# PDT3535LEDbackup.net
KiCad netlist of a schematic drawn in EAGLE
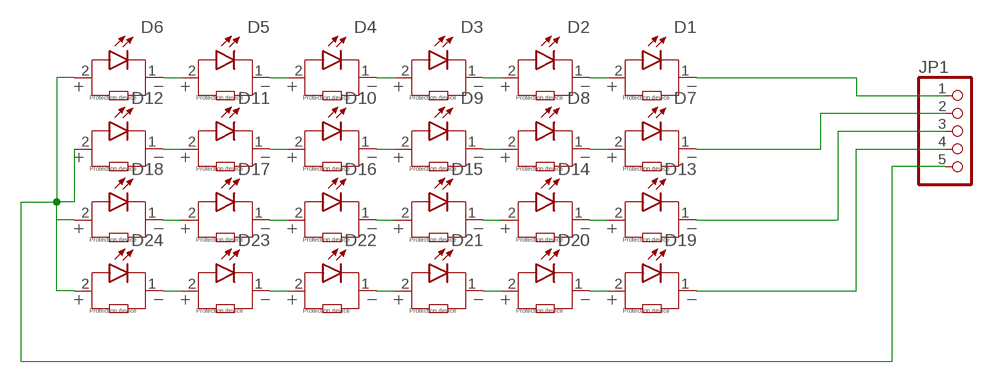
[diagram p0: schematic, sheet 1]

(export (version "E")
  (design (tool "Eeschema 10.0.6"))
  (components
    (comp (ref "D1")
      (value "WL-SWTC_3535_158353060_6000K")
      (footprint "eagle-import:WL-SWTC_3535")
      (libsource (lib "eagle-import") (part "WL-SWTC_3535_158353060_6000K"))
    )
    (comp (ref "D2")
      (value "WL-SWTC_3535_158353060_6000K")
      (footprint "eagle-import:WL-SWTC_3535")
      (libsource (lib "eagle-import") (part "WL-SWTC_3535_158353060_6000K"))
    )
    (comp (ref "D3")
      (value "WL-SWTC_3535_158353060_6000K")
      (footprint "eagle-import:WL-SWTC_3535")
      (libsource (lib "eagle-import") (part "WL-SWTC_3535_158353060_6000K"))
    )
    (comp (ref "D4")
      (value "WL-SWTC_3535_158353060_6000K")
      (footprint "eagle-import:WL-SWTC_3535")
      (libsource (lib "eagle-import") (part "WL-SWTC_3535_158353060_6000K"))
    )
    (comp (ref "D5")
      (value "WL-SWTC_3535_158353060_6000K")
      (footprint "eagle-import:WL-SWTC_3535")
      (libsource (lib "eagle-import") (part "WL-SWTC_3535_158353060_6000K"))
    )
    (comp (ref "D6")
      (value "WL-SWTC_3535_158353060_6000K")
      (footprint "eagle-import:WL-SWTC_3535")
      (libsource (lib "eagle-import") (part "WL-SWTC_3535_158353060_6000K"))
    )
    (comp (ref "D7")
      (value "WL-SWTC_3535_158353060_6000K")
      (footprint "eagle-import:WL-SWTC_3535")
      (libsource (lib "eagle-import") (part "WL-SWTC_3535_158353060_6000K"))
    )
    (comp (ref "D8")
      (value "WL-SWTC_3535_158353060_6000K")
      (footprint "eagle-import:WL-SWTC_3535")
      (libsource (lib "eagle-import") (part "WL-SWTC_3535_158353060_6000K"))
    )
    (comp (ref "D9")
      (value "WL-SWTC_3535_158353060_6000K")
      (footprint "eagle-import:WL-SWTC_3535")
      (libsource (lib "eagle-import") (part "WL-SWTC_3535_158353060_6000K"))
    )
    (comp (ref "D10")
      (value "WL-SWTC_3535_158353060_6000K")
      (footprint "eagle-import:WL-SWTC_3535")
      (libsource (lib "eagle-import") (part "WL-SWTC_3535_158353060_6000K"))
    )
    (comp (ref "D11")
      (value "WL-SWTC_3535_158353060_6000K")
      (footprint "eagle-import:WL-SWTC_3535")
      (libsource (lib "eagle-import") (part "WL-SWTC_3535_158353060_6000K"))
    )
    (comp (ref "D12")
      (value "WL-SWTC_3535_158353060_6000K")
      (footprint "eagle-import:WL-SWTC_3535")
      (libsource (lib "eagle-import") (part "WL-SWTC_3535_158353060_6000K"))
    )
    (comp (ref "D13")
      (value "WL-SWTC_3535_158353060_6000K")
      (footprint "eagle-import:WL-SWTC_3535")
      (libsource (lib "eagle-import") (part "WL-SWTC_3535_158353060_6000K"))
    )
    (comp (ref "D14")
      (value "WL-SWTC_3535_158353060_6000K")
      (footprint "eagle-import:WL-SWTC_3535")
      (libsource (lib "eagle-import") (part "WL-SWTC_3535_158353060_6000K"))
    )
    (comp (ref "D15")
      (value "WL-SWTC_3535_158353060_6000K")
      (footprint "eagle-import:WL-SWTC_3535")
      (libsource (lib "eagle-import") (part "WL-SWTC_3535_158353060_6000K"))
    )
    (comp (ref "D16")
      (value "WL-SWTC_3535_158353060_6000K")
      (footprint "eagle-import:WL-SWTC_3535")
      (libsource (lib "eagle-import") (part "WL-SWTC_3535_158353060_6000K"))
    )
    (comp (ref "D17")
      (value "WL-SWTC_3535_158353060_6000K")
      (footprint "eagle-import:WL-SWTC_3535")
      (libsource (lib "eagle-import") (part "WL-SWTC_3535_158353060_6000K"))
    )
    (comp (ref "D18")
      (value "WL-SWTC_3535_158353060_6000K")
      (footprint "eagle-import:WL-SWTC_3535")
      (libsource (lib "eagle-import") (part "WL-SWTC_3535_158353060_6000K"))
    )
    (comp (ref "D19")
      (value "WL-SWTC_3535_158353060_6000K")
      (footprint "eagle-import:WL-SWTC_3535")
      (libsource (lib "eagle-import") (part "WL-SWTC_3535_158353060_6000K"))
    )
    (comp (ref "D20")
      (value "WL-SWTC_3535_158353060_6000K")
      (footprint "eagle-import:WL-SWTC_3535")
      (libsource (lib "eagle-import") (part "WL-SWTC_3535_158353060_6000K"))
    )
    (comp (ref "D21")
      (value "WL-SWTC_3535_158353060_6000K")
      (footprint "eagle-import:WL-SWTC_3535")
      (libsource (lib "eagle-import") (part "WL-SWTC_3535_158353060_6000K"))
    )
    (comp (ref "D22")
      (value "WL-SWTC_3535_158353060_6000K")
      (footprint "eagle-import:WL-SWTC_3535")
      (libsource (lib "eagle-import") (part "WL-SWTC_3535_158353060_6000K"))
    )
    (comp (ref "D23")
      (value "WL-SWTC_3535_158353060_6000K")
      (footprint "eagle-import:WL-SWTC_3535")
      (libsource (lib "eagle-import") (part "WL-SWTC_3535_158353060_6000K"))
    )
    (comp (ref "D24")
      (value "WL-SWTC_3535_158353060_6000K")
      (footprint "eagle-import:WL-SWTC_3535")
      (libsource (lib "eagle-import") (part "WL-SWTC_3535_158353060_6000K"))
    )
    (comp (ref "JP1")
      (value "PINHD-1X05_2.54-SMD-90°")
      (footprint "eagle-import:1X05SMD_90")
      (libsource (lib "eagle-import") (part "PINHD-1X05_2.54-SMD-90°"))
    )
  )
  (nets
    (net (code "1") (name "Net-(D1-Pad1)") (class "Default")
      (node (ref "D1") (pin "1") (pinfunction "1_1") (pintype "passive"))
      (node (ref "JP1") (pin "1") (pinfunction "1_1") (pintype "passive"))
    )
    (net (code "2") (name "Net-(D1-Pad2)") (class "Default")
      (node (ref "D1") (pin "2") (pinfunction "2_2") (pintype "passive"))
      (node (ref "D2") (pin "1") (pinfunction "1_1") (pintype "passive"))
    )
    (net (code "3") (name "Net-(D2-Pad2)") (class "Default")
      (node (ref "D2") (pin "2") (pinfunction "2_2") (pintype "passive"))
      (node (ref "D3") (pin "1") (pinfunction "1_1") (pintype "passive"))
    )
    (net (code "4") (name "Net-(D3-Pad2)") (class "Default")
      (node (ref "D3") (pin "2") (pinfunction "2_2") (pintype "passive"))
      (node (ref "D4") (pin "1") (pinfunction "1_1") (pintype "passive"))
    )
    (net (code "5") (name "Net-(D4-Pad2)") (class "Default")
      (node (ref "D4") (pin "2") (pinfunction "2_2") (pintype "passive"))
      (node (ref "D5") (pin "1") (pinfunction "1_1") (pintype "passive"))
    )
    (net (code "6") (name "Net-(D5-Pad2)") (class "Default")
      (node (ref "D5") (pin "2") (pinfunction "2_2") (pintype "passive"))
      (node (ref "D6") (pin "1") (pinfunction "1_1") (pintype "passive"))
    )
    (net (code "7") (name "Net-(D7-Pad1)") (class "Default")
      (node (ref "D7") (pin "1") (pinfunction "1_1") (pintype "passive"))
      (node (ref "JP1") (pin "2") (pinfunction "2_2") (pintype "passive"))
    )
    (net (code "8") (name "Net-(D7-Pad2)") (class "Default")
      (node (ref "D7") (pin "2") (pinfunction "2_2") (pintype "passive"))
      (node (ref "D8") (pin "1") (pinfunction "1_1") (pintype "passive"))
    )
    (net (code "9") (name "Net-(D8-Pad2)") (class "Default")
      (node (ref "D8") (pin "2") (pinfunction "2_2") (pintype "passive"))
      (node (ref "D9") (pin "1") (pinfunction "1_1") (pintype "passive"))
    )
    (net (code "10") (name "Net-(D10-Pad1)") (class "Default")
      (node (ref "D10") (pin "1") (pinfunction "1_1") (pintype "passive"))
      (node (ref "D9") (pin "2") (pinfunction "2_2") (pintype "passive"))
    )
    (net (code "11") (name "Net-(D10-Pad2)") (class "Default")
      (node (ref "D10") (pin "2") (pinfunction "2_2") (pintype "passive"))
      (node (ref "D11") (pin "1") (pinfunction "1_1") (pintype "passive"))
    )
    (net (code "12") (name "Net-(D11-Pad2)") (class "Default")
      (node (ref "D11") (pin "2") (pinfunction "2_2") (pintype "passive"))
      (node (ref "D12") (pin "1") (pinfunction "1_1") (pintype "passive"))
    )
    (net (code "13") (name "Net-(D12-Pad2)") (class "Default")
      (node (ref "D12") (pin "2") (pinfunction "2_2") (pintype "passive"))
      (node (ref "D18") (pin "2") (pinfunction "2_2") (pintype "passive"))
      (node (ref "D24") (pin "2") (pinfunction "2_2") (pintype "passive"))
      (node (ref "D6") (pin "2") (pinfunction "2_2") (pintype "passive"))
      (node (ref "JP1") (pin "5") (pinfunction "5_5") (pintype "passive"))
    )
    (net (code "14") (name "Net-(D13-Pad1)") (class "Default")
      (node (ref "D13") (pin "1") (pinfunction "1_1") (pintype "passive"))
      (node (ref "JP1") (pin "3") (pinfunction "3_3") (pintype "passive"))
    )
    (net (code "15") (name "Net-(D13-Pad2)") (class "Default")
      (node (ref "D13") (pin "2") (pinfunction "2_2") (pintype "passive"))
      (node (ref "D14") (pin "1") (pinfunction "1_1") (pintype "passive"))
    )
    (net (code "16") (name "Net-(D14-Pad2)") (class "Default")
      (node (ref "D14") (pin "2") (pinfunction "2_2") (pintype "passive"))
      (node (ref "D15") (pin "1") (pinfunction "1_1") (pintype "passive"))
    )
    (net (code "17") (name "Net-(D15-Pad2)") (class "Default")
      (node (ref "D15") (pin "2") (pinfunction "2_2") (pintype "passive"))
      (node (ref "D16") (pin "1") (pinfunction "1_1") (pintype "passive"))
    )
    (net (code "18") (name "Net-(D16-Pad2)") (class "Default")
      (node (ref "D16") (pin "2") (pinfunction "2_2") (pintype "passive"))
      (node (ref "D17") (pin "1") (pinfunction "1_1") (pintype "passive"))
    )
    (net (code "19") (name "Net-(D17-Pad2)") (class "Default")
      (node (ref "D17") (pin "2") (pinfunction "2_2") (pintype "passive"))
      (node (ref "D18") (pin "1") (pinfunction "1_1") (pintype "passive"))
    )
    (net (code "20") (name "Net-(D19-Pad1)") (class "Default")
      (node (ref "D19") (pin "1") (pinfunction "1_1") (pintype "passive"))
      (node (ref "JP1") (pin "4") (pinfunction "4_4") (pintype "passive"))
    )
    (net (code "21") (name "Net-(D19-Pad2)") (class "Default")
      (node (ref "D19") (pin "2") (pinfunction "2_2") (pintype "passive"))
      (node (ref "D20") (pin "1") (pinfunction "1_1") (pintype "passive"))
    )
    (net (code "22") (name "Net-(D20-Pad2)") (class "Default")
      (node (ref "D20") (pin "2") (pinfunction "2_2") (pintype "passive"))
      (node (ref "D21") (pin "1") (pinfunction "1_1") (pintype "passive"))
    )
    (net (code "23") (name "Net-(D21-Pad2)") (class "Default")
      (node (ref "D21") (pin "2") (pinfunction "2_2") (pintype "passive"))
      (node (ref "D22") (pin "1") (pinfunction "1_1") (pintype "passive"))
    )
    (net (code "24") (name "Net-(D22-Pad2)") (class "Default")
      (node (ref "D22") (pin "2") (pinfunction "2_2") (pintype "passive"))
      (node (ref "D23") (pin "1") (pinfunction "1_1") (pintype "passive"))
    )
    (net (code "25") (name "Net-(D23-Pad2)") (class "Default")
      (node (ref "D23") (pin "2") (pinfunction "2_2") (pintype "passive"))
      (node (ref "D24") (pin "1") (pinfunction "1_1") (pintype "passive"))
    )
  )
)
